# MotorControl.net
KiCad netlist of a schematic drawn in Altium Designer
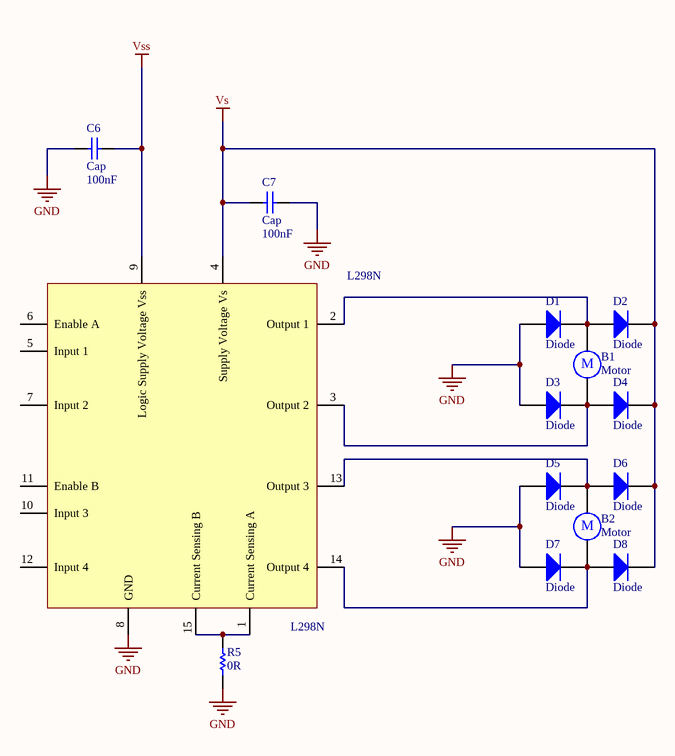
[diagram p0: MotorControl.SchDoc]

(export (version "E")
  (design (tool "Eeschema 10.0.6"))
  (components
    (comp (ref "B1")
      (value "Motor")
      (footprint "RB5-10.5")
      (description "Motor, General Kind")
      (fields (field (name "PUBLISHER") "Altium Limited"))
      (libsource (lib "Miscellaneous Devices") (part "Motor"))
    )
    (comp (ref "B2")
      (value "Motor")
      (footprint "RB5-10.5")
      (description "Motor, General Kind")
      (fields (field (name "PUBLISHER") "Altium Limited"))
      (libsource (lib "Miscellaneous Devices") (part "Motor"))
    )
    (comp (ref "C6")
      (value "Cap")
      (footprint "RAD-0.3")
      (description "Capacitor")
      (fields (field (name "ALTIUM_VALUE") "100nF") (field (name "PUBLISHER") "Altium Limited"))
      (libsource (lib "Miscellaneous Devices") (part "Cap"))
    )
    (comp (ref "C7")
      (value "Cap")
      (footprint "RAD-0.3")
      (description "Capacitor")
      (fields (field (name "ALTIUM_VALUE") "100nF") (field (name "PUBLISHER") "Altium Limited"))
      (libsource (lib "Miscellaneous Devices") (part "Cap"))
    )
    (comp (ref "D1")
      (value "Diode")
      (footprint "SMC")
      (description "Default Diode")
      (fields (field (name "PUBLISHER") "Altium Limited"))
      (libsource (lib "Miscellaneous Devices") (part "Diode"))
    )
    (comp (ref "D2")
      (value "Diode")
      (footprint "SMC")
      (description "Default Diode")
      (fields (field (name "PUBLISHER") "Altium Limited"))
      (libsource (lib "Miscellaneous Devices") (part "Diode"))
    )
    (comp (ref "D3")
      (value "Diode")
      (footprint "SMC")
      (description "Default Diode")
      (fields (field (name "PUBLISHER") "Altium Limited"))
      (libsource (lib "Miscellaneous Devices") (part "Diode"))
    )
    (comp (ref "D4")
      (value "Diode")
      (footprint "SMC")
      (description "Default Diode")
      (fields (field (name "PUBLISHER") "Altium Limited"))
      (libsource (lib "Miscellaneous Devices") (part "Diode"))
    )
    (comp (ref "D5")
      (value "Diode")
      (footprint "SMC")
      (description "Default Diode")
      (fields (field (name "PUBLISHER") "Altium Limited"))
      (libsource (lib "Miscellaneous Devices") (part "Diode"))
    )
    (comp (ref "D6")
      (value "Diode")
      (footprint "SMC")
      (description "Default Diode")
      (fields (field (name "PUBLISHER") "Altium Limited"))
      (libsource (lib "Miscellaneous Devices") (part "Diode"))
    )
    (comp (ref "D7")
      (value "Diode")
      (footprint "SMC")
      (description "Default Diode")
      (fields (field (name "PUBLISHER") "Altium Limited"))
      (libsource (lib "Miscellaneous Devices") (part "Diode"))
    )
    (comp (ref "D8")
      (value "Diode")
      (footprint "SMC")
      (description "Default Diode")
      (fields (field (name "PUBLISHER") "Altium Limited"))
      (libsource (lib "Miscellaneous Devices") (part "Diode"))
    )
    (comp (ref "L298N") (value "L298N") (footprint "L298N") (libsource (lib "SCHLIB_Autobot") (part "L298N")))
    (comp (ref "R5")
      (value "0R")
      (footprint "AXIAL-0.3")
      (description "Resistor")
      (fields (field (name "PUBLISHER") "Altium Limited"))
      (libsource (lib "Miscellaneous Devices") (part "Res1"))
    )
  )
  (nets
    (net (code "1") (name "GND") (class "Default")
      (node (ref "C6") (pin "2") (pinfunction "2_2") (pintype "passive"))
      (node (ref "C7") (pin "2") (pinfunction "2_2") (pintype "passive"))
      (node (ref "D1") (pin "1") (pinfunction "A_1") (pintype "passive"))
      (node (ref "D3") (pin "1") (pinfunction "A_1") (pintype "passive"))
      (node (ref "D5") (pin "1") (pinfunction "A_1") (pintype "passive"))
      (node (ref "D7") (pin "1") (pinfunction "A_1") (pintype "passive"))
      (node (ref "L298N") (pin "8") (pinfunction "GND_8") (pintype "passive"))
      (node (ref "R5") (pin "1") (pinfunction "1_1") (pintype "passive"))
    )
    (net (code "2") (name "Net-(D1-K)") (class "Default")
      (node (ref "B1") (pin "1") (pinfunction "1_1") (pintype "passive"))
      (node (ref "D1") (pin "2") (pinfunction "K_2") (pintype "passive"))
      (node (ref "D2") (pin "1") (pinfunction "A_1") (pintype "passive"))
      (node (ref "L298N") (pin "2") (pinfunction "Output_1_2") (pintype "passive"))
    )
    (net (code "3") (name "Net-(D3-K)") (class "Default")
      (node (ref "B1") (pin "2") (pinfunction "2_2") (pintype "passive"))
      (node (ref "D3") (pin "2") (pinfunction "K_2") (pintype "passive"))
      (node (ref "D4") (pin "1") (pinfunction "A_1") (pintype "passive"))
      (node (ref "L298N") (pin "3") (pinfunction "Output_2_3") (pintype "passive"))
    )
    (net (code "4") (name "Net-(D5-K)") (class "Default")
      (node (ref "B2") (pin "1") (pinfunction "1_1") (pintype "passive"))
      (node (ref "D5") (pin "2") (pinfunction "K_2") (pintype "passive"))
      (node (ref "D6") (pin "1") (pinfunction "A_1") (pintype "passive"))
      (node (ref "L298N") (pin "13") (pinfunction "Output_3_13") (pintype "passive"))
    )
    (net (code "5") (name "Net-(D7-K)") (class "Default")
      (node (ref "B2") (pin "2") (pinfunction "2_2") (pintype "passive"))
      (node (ref "D7") (pin "2") (pinfunction "K_2") (pintype "passive"))
      (node (ref "D8") (pin "1") (pinfunction "A_1") (pintype "passive"))
      (node (ref "L298N") (pin "14") (pinfunction "Output_4_14") (pintype "passive"))
    )
    (net (code "6") (name "Net-(L298N-Current_Sensing_A)") (class "Default")
      (node (ref "L298N") (pin "1") (pinfunction "Current_Sensing_A_1") (pintype "passive"))
      (node (ref "L298N") (pin "15") (pinfunction "Current_Sensing_B_15") (pintype "passive"))
      (node (ref "R5") (pin "2") (pinfunction "2_2") (pintype "passive"))
    )
    (net (code "7") (name "Vs") (class "Default")
      (node (ref "C7") (pin "1") (pinfunction "1_1") (pintype "passive"))
      (node (ref "D2") (pin "2") (pinfunction "K_2") (pintype "passive"))
      (node (ref "D4") (pin "2") (pinfunction "K_2") (pintype "passive"))
      (node (ref "D6") (pin "2") (pinfunction "K_2") (pintype "passive"))
      (node (ref "D8") (pin "2") (pinfunction "K_2") (pintype "passive"))
      (node (ref "L298N") (pin "4") (pinfunction "Supply_Voltage_Vs_4") (pintype "passive"))
    )
    (net (code "8") (name "Vss") (class "Default")
      (node (ref "C6") (pin "1") (pinfunction "1_1") (pintype "passive"))
      (node (ref "L298N") (pin "9") (pinfunction "Logic_Supply_Voltage_Vss_9") (pintype "passive"))
    )
    (net (code "9") (name "unconnected-(L298N-Enable_A-Pad6)") (class "Default")
      (node (ref "L298N") (pin "6") (pinfunction "Enable_A_6") (pintype "passive"))
    )
    (net (code "10") (name "unconnected-(L298N-Enable_B-Pad11)") (class "Default")
      (node (ref "L298N") (pin "11") (pinfunction "Enable_B_11") (pintype "passive"))
    )
    (net (code "11") (name "unconnected-(L298N-Input_1-Pad5)") (class "Default")
      (node (ref "L298N") (pin "5") (pinfunction "Input_1_5") (pintype "passive"))
    )
    (net (code "12") (name "unconnected-(L298N-Input_2-Pad7)") (class "Default")
      (node (ref "L298N") (pin "7") (pinfunction "Input_2_7") (pintype "passive"))
    )
    (net (code "13") (name "unconnected-(L298N-Input_3-Pad10)") (class "Default")
      (node (ref "L298N") (pin "10") (pinfunction "Input_3_10") (pintype "passive"))
    )
    (net (code "14") (name "unconnected-(L298N-Input_4-Pad12)") (class "Default")
      (node (ref "L298N") (pin "12") (pinfunction "Input_4_12") (pintype "passive"))
    )
  )
)
